# SH6_-_CAN.net
KiCad netlist of a schematic drawn in Altium Designer
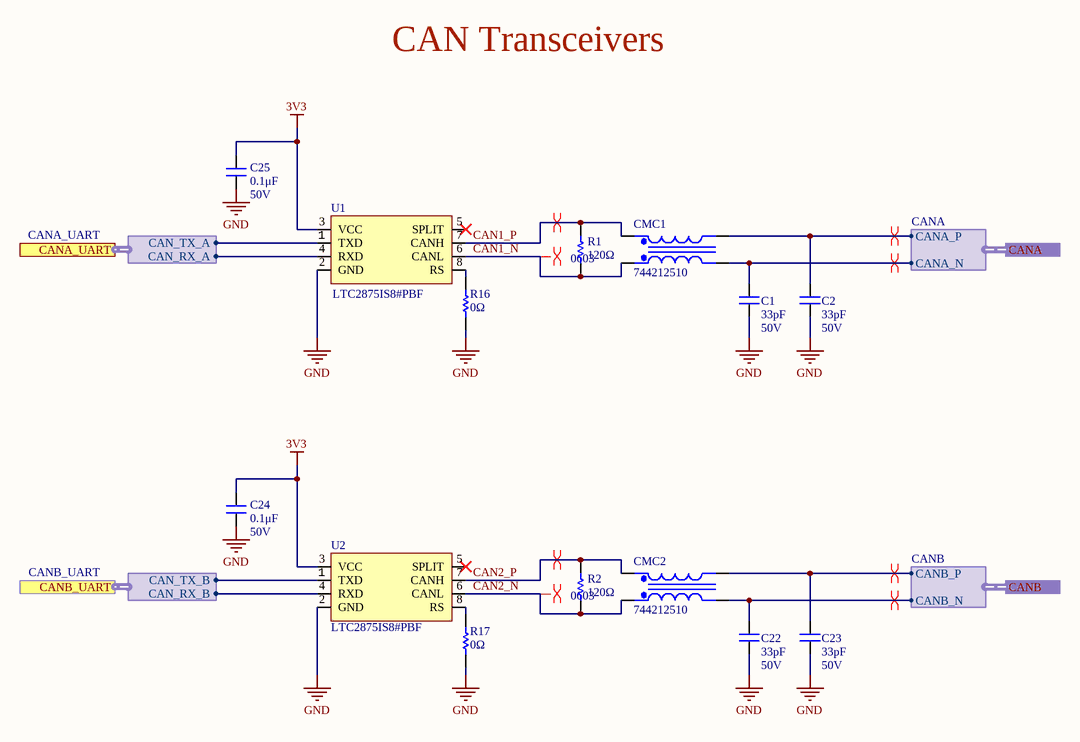
[diagram p0: SH6 - CAN.SchDoc]

(export (version "E")
  (design (tool "Eeschema 10.0.6"))
  (components
    (comp (ref "C1")
      (value "33pF")
      (footprint "CAP0603")
      (description "CAP CER 33PF 50V C0G/NP0")
      (fields
        (field (name "TOLERANCE") "5%")
        (field (name "VOLTAGE") "50V")
        (field (name "Comment") "CAP_33pF_50V_0603")
      )
      (libsource (lib "UWRT_Schematic_Library_2020") (part "CAP_33pF_50V_0603"))
    )
    (comp (ref "C2")
      (value "33pF")
      (footprint "CAP0603")
      (description "CAP CER 33PF 50V C0G/NP0")
      (fields
        (field (name "TOLERANCE") "5%")
        (field (name "VOLTAGE") "50V")
        (field (name "Comment") "CAP_33pF_50V_0603")
      )
      (libsource (lib "UWRT_Schematic_Library_2020") (part "CAP_33pF_50V_0603"))
    )
    (comp (ref "C22")
      (value "33pF")
      (footprint "CAP0603")
      (description "CAP CER 33PF 50V C0G/NP0")
      (fields
        (field (name "TOLERANCE") "5%")
        (field (name "VOLTAGE") "50V")
        (field (name "Comment") "CAP_33pF_50V_0603")
      )
      (libsource (lib "UWRT_Schematic_Library_2020") (part "CAP_33pF_50V_0603"))
    )
    (comp (ref "C23")
      (value "33pF")
      (footprint "CAP0603")
      (description "CAP CER 33PF 50V C0G/NP0")
      (fields
        (field (name "TOLERANCE") "5%")
        (field (name "VOLTAGE") "50V")
        (field (name "Comment") "CAP_33pF_50V_0603")
      )
      (libsource (lib "UWRT_Schematic_Library_2020") (part "CAP_33pF_50V_0603"))
    )
    (comp (ref "C24")
      (value "0.1μF")
      (footprint "CAP0603")
      (description "CAP CER 0.1UF 50V X7R 0603")
      (fields (field (name "VOLTAGE RATING") "50V") (field (name "Comment") "CAP_0.1uF_50V_0603"))
      (libsource (lib "UWRT_Schematic_Library_2020") (part "CAP_0.1uF_50V_0603"))
    )
    (comp (ref "C25")
      (value "0.1μF")
      (footprint "CAP0603")
      (description "CAP CER 0.1UF 50V X7R 0603")
      (fields (field (name "VOLTAGE RATING") "50V") (field (name "Comment") "CAP_0.1uF_50V_0603"))
      (libsource (lib "UWRT_Schematic_Library_2020") (part "CAP_0.1uF_50V_0603"))
    )
    (comp (ref "CMC1")
      (value "CMC_51uH")
      (footprint "744212510")
      (description "CMC 51uH 300MA 2LN SMD")
      (fields (field (name "MANUFACTURER PART NUMBER 1") "744212510") (field (name "TOLERANCE") "50%"))
      (libsource (lib "UWRT_Schematic_Library_2020") (part "CMC_51uH"))
    )
    (comp (ref "CMC2")
      (value "CMC_51uH")
      (footprint "744212510")
      (description "CMC 51uH 300MA 2LN SMD")
      (fields (field (name "MANUFACTURER PART NUMBER 1") "744212510") (field (name "TOLERANCE") "50%"))
      (libsource (lib "UWRT_Schematic_Library_2020") (part "CMC_51uH"))
    )
    (comp (ref "R1")
      (value "120Ω")
      (footprint "RESC0603")
      (description "RES 120 OHM 5% 1/10W 0603")
      (fields (field (name "PACKAGE/FOOTPRINT") "0603") (field (name "Comment") "RES_120Ω_0603"))
      (libsource (lib "UWRT_Schematic_Library_2020") (part "RES_120Ω_0603_5%"))
    )
    (comp (ref "R2")
      (value "120Ω")
      (footprint "RESC0603")
      (description "RES 120 OHM 5% 1/10W 0603")
      (fields (field (name "PACKAGE/FOOTPRINT") "0603") (field (name "Comment") "RES_120Ω_0603"))
      (libsource (lib "UWRT_Schematic_Library_2020") (part "RES_120Ω_0603_5%"))
    )
    (comp (ref "R16")
      (value "0Ω")
      (footprint "RESC0603")
      (description "RES 0 OHM JUMPER 1/10W 0603")
      (fields (field (name "Comment") "RES_0Ω_0603"))
      (libsource (lib "UWRT_Schematic_Library_2020") (part "RES_0Ω_0603"))
    )
    (comp (ref "R17")
      (value "0Ω")
      (footprint "RESC0603")
      (description "RES 0 OHM JUMPER 1/10W 0603")
      (fields (field (name "Comment") "RES_0Ω_0603"))
      (libsource (lib "UWRT_Schematic_Library_2020") (part "RES_0Ω_0603"))
    )
    (comp (ref "U1")
      (value "LTC2875")
      (footprint "LT-S8_N")
      (description "IC TXRX CAN 4MBPS 8SO")
      (fields
        (field (name "MANUFACTURER PART NUMBER 1") "LTC2875IS8#PBF")
        (field (name "LCSC PART #") "C117076")
      )
      (libsource (lib "UWRT_Schematic_Library_2020") (part "LTC2875"))
    )
    (comp (ref "U2")
      (value "LTC2875")
      (footprint "LT-S8_N")
      (description "IC TXRX CAN 4MBPS 8SO")
      (fields
        (field (name "MANUFACTURER PART NUMBER 1") "LTC2875IS8#PBF")
        (field (name "LCSC PART #") "C117076")
      )
      (libsource (lib "UWRT_Schematic_Library_2020") (part "LTC2875"))
    )
  )
  (nets
    (net (code "5") (name "/CAN1_N") (class "Default")
      (node (ref "CMC1") (pin "1") (pinfunction "Pri+_1") (pintype "passive"))
      (node (ref "R1") (pin "1") (pinfunction "1_1") (pintype "passive"))
      (node (ref "U1") (pin "6") (pinfunction "CANL_6") (pintype "passive"))
    )
    (net (code "6") (name "/CAN1_P") (class "Default")
      (node (ref "CMC1") (pin "3") (pinfunction "Sec+_3") (pintype "passive"))
      (node (ref "R1") (pin "2") (pinfunction "2_2") (pintype "passive"))
      (node (ref "U1") (pin "7") (pinfunction "CANH_7") (pintype "passive"))
    )
    (net (code "7") (name "/CAN2_N") (class "Default")
      (node (ref "CMC2") (pin "1") (pinfunction "Pri+_1") (pintype "passive"))
      (node (ref "R2") (pin "1") (pinfunction "1_1") (pintype "passive"))
      (node (ref "U2") (pin "6") (pinfunction "CANL_6") (pintype "passive"))
    )
    (net (code "8") (name "/CAN2_P") (class "Default")
      (node (ref "CMC2") (pin "3") (pinfunction "Sec+_3") (pintype "passive"))
      (node (ref "R2") (pin "2") (pinfunction "2_2") (pintype "passive"))
      (node (ref "U2") (pin "7") (pinfunction "CANH_7") (pintype "passive"))
    )
    (net (code "9") (name "/CANA_N") (class "Default")
      (node (ref "C1") (pin "2") (pinfunction "2_2") (pintype "passive"))
      (node (ref "CMC1") (pin "5") (pinfunction "Pri-_5") (pintype "passive"))
    )
    (net (code "10") (name "/CANA_P") (class "Default")
      (node (ref "C2") (pin "2") (pinfunction "2_2") (pintype "passive"))
      (node (ref "CMC1") (pin "4") (pinfunction "Sec-_4") (pintype "passive"))
    )
    (net (code "11") (name "/CANB_N") (class "Default")
      (node (ref "C22") (pin "2") (pinfunction "2_2") (pintype "passive"))
      (node (ref "CMC2") (pin "5") (pinfunction "Pri-_5") (pintype "passive"))
    )
    (net (code "12") (name "/CANB_P") (class "Default")
      (node (ref "C23") (pin "2") (pinfunction "2_2") (pintype "passive"))
      (node (ref "CMC2") (pin "4") (pinfunction "Sec-_4") (pintype "passive"))
    )
    (net (code "13") (name "/CAN_RX_A") (class "Default")
      (node (ref "U1") (pin "4") (pinfunction "RXD_4") (pintype "passive"))
    )
    (net (code "14") (name "/CAN_RX_B") (class "Default")
      (node (ref "U2") (pin "4") (pinfunction "RXD_4") (pintype "passive"))
    )
    (net (code "15") (name "/CAN_TX_A") (class "Default")
      (node (ref "U1") (pin "1") (pinfunction "TXD_1") (pintype "passive"))
    )
    (net (code "16") (name "/CAN_TX_B") (class "Default")
      (node (ref "U2") (pin "1") (pinfunction "TXD_1") (pintype "passive"))
    )
    (net (code "21") (name "3V3") (class "Default")
      (node (ref "C24") (pin "1") (pinfunction "1_1") (pintype "passive"))
      (node (ref "C25") (pin "1") (pinfunction "1_1") (pintype "passive"))
      (node (ref "U1") (pin "3") (pinfunction "VCC_3") (pintype "passive"))
      (node (ref "U2") (pin "3") (pinfunction "VCC_3") (pintype "passive"))
    )
    (net (code "22") (name "GND") (class "Default")
      (node (ref "C1") (pin "1") (pinfunction "1_1") (pintype "passive"))
      (node (ref "C2") (pin "1") (pinfunction "1_1") (pintype "passive"))
      (node (ref "C22") (pin "1") (pinfunction "1_1") (pintype "passive"))
      (node (ref "C23") (pin "1") (pinfunction "1_1") (pintype "passive"))
      (node (ref "C24") (pin "2") (pinfunction "2_2") (pintype "passive"))
      (node (ref "C25") (pin "2") (pinfunction "2_2") (pintype "passive"))
      (node (ref "R16") (pin "1") (pinfunction "1_1") (pintype "passive"))
      (node (ref "R17") (pin "1") (pinfunction "1_1") (pintype "passive"))
      (node (ref "U1") (pin "2") (pinfunction "GND_2") (pintype "passive"))
      (node (ref "U2") (pin "2") (pinfunction "GND_2") (pintype "passive"))
    )
    (net (code "23") (name "Net-(U1-RS)") (class "Default")
      (node (ref "R16") (pin "2") (pinfunction "2_2") (pintype "passive"))
      (node (ref "U1") (pin "8") (pinfunction "RS_8") (pintype "passive"))
    )
    (net (code "24") (name "Net-(U2-RS)") (class "Default")
      (node (ref "R17") (pin "2") (pinfunction "2_2") (pintype "passive"))
      (node (ref "U2") (pin "8") (pinfunction "RS_8") (pintype "passive"))
    )
    (net (code "25") (name "unconnected-(U1-SPLIT-Pad5)") (class "Default")
      (node (ref "U1") (pin "5") (pinfunction "SPLIT_5") (pintype "passive+no_connect"))
    )
    (net (code "26") (name "unconnected-(U2-SPLIT-Pad5)") (class "Default")
      (node (ref "U2") (pin "5") (pinfunction "SPLIT_5") (pintype "passive+no_connect"))
    )
  )
)
